# montaj_nrf24l01.net
KiCad netlist of a schematic drawn in EAGLE
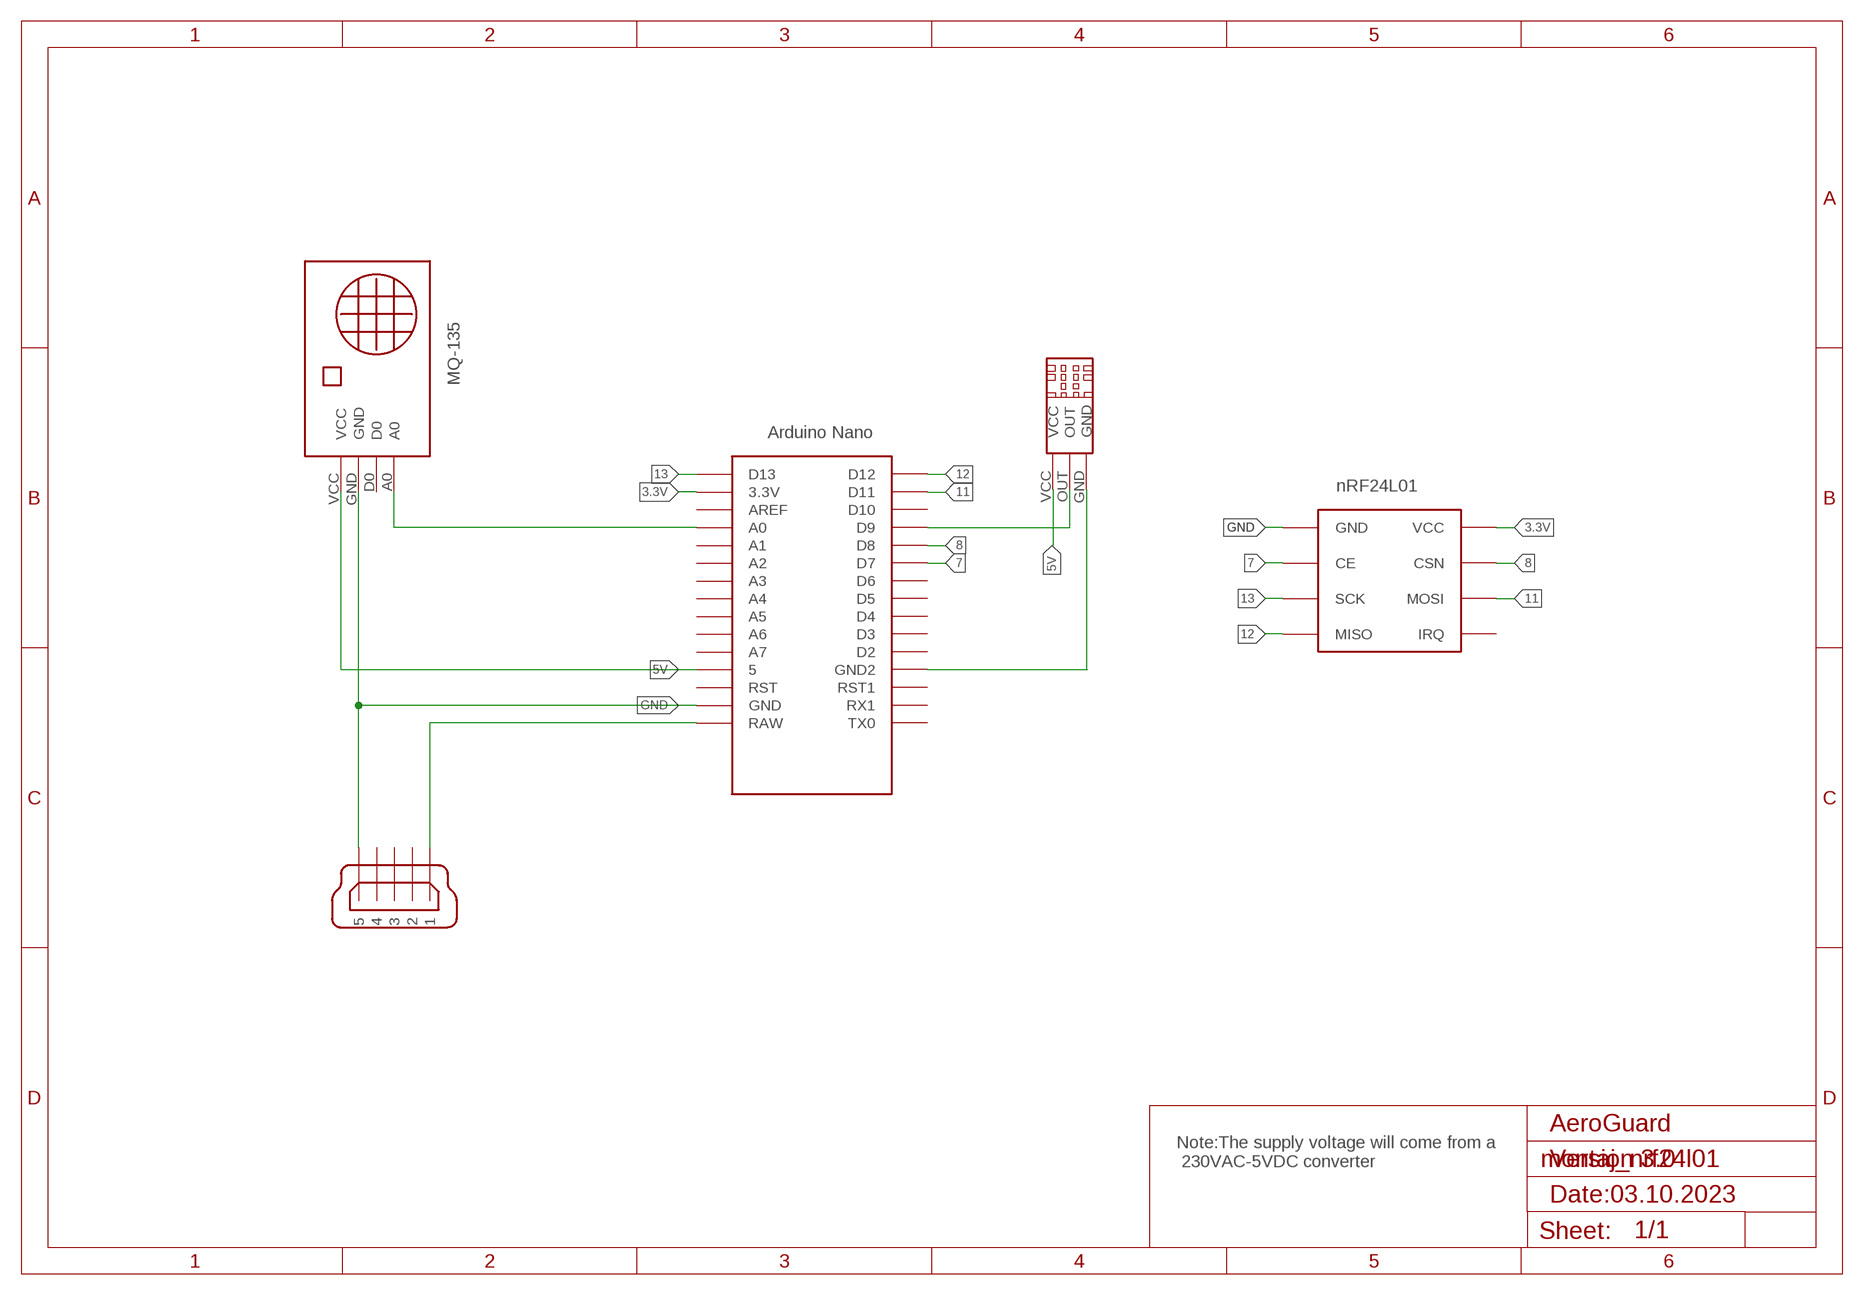
[diagram p0: schematic, sheet 1]

(export (version "E")
  (design (tool "Eeschema 10.0.6"))
  (components
    (comp (ref "GND")
      (value "NANO")
      (footprint "eagle-import:NANO")
      (libsource (lib "eagle-import") (part "NANO"))
    )
    (comp (ref "U$1")
      (value "DHT11")
      (footprint "eagle-import:DHT11")
      (libsource (lib "eagle-import") (part "DHT11"))
    )
    (comp (ref "U$2")
      (value "DEV")
      (footprint "eagle-import:FOOT")
      (libsource (lib "eagle-import") (part "DEV"))
    )
    (comp (ref "U$3")
      (value "NRF24L01")
      (footprint "eagle-import:NRF24L01")
      (libsource (lib "eagle-import") (part "NRF24L01"))
    )
    (comp (ref "X1")
      (value "MINI-USB-SHIELD-UX60-MB-5S8")
      (footprint "eagle-import:UX60-MB-5S8")
      (libsource (lib "eagle-import") (part "MINI-USB-SHIELD-UX60-MB-5S8"))
    )
  )
  (nets
    (net (code "1") (name "3.3V") (class "Default")
      (node (ref "U$3") (pin "VCC") (pinfunction "VCC_VCC") (pintype "bidirectional"))
    )
    (net (code "2") (name "5V") (class "Default")
      (node (ref "GND") (pin "5V") (pinfunction "5_5V") (pintype "bidirectional"))
      (node (ref "U$2") (pin "VCC") (pinfunction "VCC_VCC") (pintype "bidirectional"))
    )
    (net (code "3") (name "7") (class "Default")
      (node (ref "U$3") (pin "CE") (pinfunction "CE_CE") (pintype "bidirectional"))
    )
    (net (code "4") (name "8") (class "Default")
      (node (ref "U$3") (pin "CSN") (pinfunction "CSN_CSN") (pintype "bidirectional"))
    )
    (net (code "5") (name "11") (class "Default")
      (node (ref "U$3") (pin "MOSI") (pinfunction "MOSI_MOSI") (pintype "bidirectional"))
    )
    (net (code "6") (name "12") (class "Default")
      (node (ref "U$3") (pin "MISO") (pinfunction "MISO_MISO") (pintype "bidirectional"))
    )
    (net (code "7") (name "13") (class "Default")
      (node (ref "U$3") (pin "SCK") (pinfunction "SCK_SCK") (pintype "bidirectional"))
    )
    (net (code "8") (name "GND") (class "Default")
      (node (ref "U$3") (pin "GND") (pinfunction "GND_GND") (pintype "bidirectional"))
    )
    (net (code "9") (name "Net-(GND-GND2)") (class "Default")
      (node (ref "GND") (pin "GND1") (pinfunction "GND2_GND1") (pintype "bidirectional"))
      (node (ref "U$1") (pin "GND") (pinfunction "GND_GND") (pintype "bidirectional"))
    )
    (net (code "10") (name "Net-(GND-PadA0)") (class "Default")
      (node (ref "GND") (pin "A0") (pinfunction "A0_A0") (pintype "bidirectional"))
      (node (ref "U$2") (pin "A0") (pinfunction "A0_A0") (pintype "bidirectional"))
    )
    (net (code "11") (name "Net-(GND-PadD9)") (class "Default")
      (node (ref "GND") (pin "D9") (pinfunction "D9_D9") (pintype "bidirectional"))
      (node (ref "U$1") (pin "OUT") (pinfunction "OUT_OUT") (pintype "bidirectional"))
    )
    (net (code "12") (name "Net-(GND-PadGND)") (class "Default")
      (node (ref "GND") (pin "GND") (pinfunction "GND_GND") (pintype "bidirectional"))
      (node (ref "U$2") (pin "GND") (pinfunction "GND_GND") (pintype "bidirectional"))
      (node (ref "X1") (pin "5") (pinfunction "5_5") (pintype "input"))
    )
    (net (code "13") (name "Net-(GND-PadRAW)") (class "Default")
      (node (ref "GND") (pin "RAW") (pinfunction "RAW_RAW") (pintype "bidirectional"))
      (node (ref "X1") (pin "1") (pinfunction "1_1") (pintype "input"))
    )
    (net (code "14") (name "unconnected-(GND-Pad3.3V)") (class "Default")
      (node (ref "GND") (pin "3.3V") (pinfunction "3.3V_3.3V") (pintype "bidirectional"))
    )
    (net (code "15") (name "unconnected-(GND-PadA1)") (class "Default")
      (node (ref "GND") (pin "A1") (pinfunction "A1_A1") (pintype "bidirectional"))
    )
    (net (code "16") (name "unconnected-(GND-PadA2)") (class "Default")
      (node (ref "GND") (pin "A2") (pinfunction "A2_A2") (pintype "bidirectional"))
    )
    (net (code "17") (name "unconnected-(GND-PadA3)") (class "Default")
      (node (ref "GND") (pin "A3") (pinfunction "A3_A3") (pintype "bidirectional"))
    )
    (net (code "18") (name "unconnected-(GND-PadA4)") (class "Default")
      (node (ref "GND") (pin "A4") (pinfunction "A4_A4") (pintype "bidirectional"))
    )
    (net (code "19") (name "unconnected-(GND-PadA5)") (class "Default")
      (node (ref "GND") (pin "A5") (pinfunction "A5_A5") (pintype "bidirectional"))
    )
    (net (code "20") (name "unconnected-(GND-PadA6)") (class "Default")
      (node (ref "GND") (pin "A6") (pinfunction "A6_A6") (pintype "bidirectional"))
    )
    (net (code "21") (name "unconnected-(GND-PadA7)") (class "Default")
      (node (ref "GND") (pin "A7") (pinfunction "A7_A7") (pintype "bidirectional"))
    )
    (net (code "22") (name "unconnected-(GND-PadAREF)") (class "Default")
      (node (ref "GND") (pin "AREF") (pinfunction "AREF_AREF") (pintype "bidirectional"))
    )
    (net (code "23") (name "unconnected-(GND-PadD2)") (class "Default")
      (node (ref "GND") (pin "D2") (pinfunction "D2_D2") (pintype "bidirectional"))
    )
    (net (code "24") (name "unconnected-(GND-PadD3)") (class "Default")
      (node (ref "GND") (pin "D3") (pinfunction "D3_D3") (pintype "bidirectional"))
    )
    (net (code "25") (name "unconnected-(GND-PadD4)") (class "Default")
      (node (ref "GND") (pin "D4") (pinfunction "D4_D4") (pintype "bidirectional"))
    )
    (net (code "26") (name "unconnected-(GND-PadD5)") (class "Default")
      (node (ref "GND") (pin "D5") (pinfunction "D5_D5") (pintype "bidirectional"))
    )
    (net (code "27") (name "unconnected-(GND-PadD6)") (class "Default")
      (node (ref "GND") (pin "D6") (pinfunction "D6_D6") (pintype "bidirectional"))
    )
    (net (code "28") (name "unconnected-(GND-PadD7)") (class "Default")
      (node (ref "GND") (pin "D7") (pinfunction "D7_D7") (pintype "bidirectional"))
    )
    (net (code "29") (name "unconnected-(GND-PadD8)") (class "Default")
      (node (ref "GND") (pin "D8") (pinfunction "D8_D8") (pintype "bidirectional"))
    )
    (net (code "30") (name "unconnected-(GND-PadD10)") (class "Default")
      (node (ref "GND") (pin "D10") (pinfunction "D10_D10") (pintype "bidirectional"))
    )
    (net (code "31") (name "unconnected-(GND-PadD11)") (class "Default")
      (node (ref "GND") (pin "D11") (pinfunction "D11_D11") (pintype "bidirectional"))
    )
    (net (code "32") (name "unconnected-(GND-PadD12)") (class "Default")
      (node (ref "GND") (pin "D12") (pinfunction "D12_D12") (pintype "bidirectional"))
    )
    (net (code "33") (name "unconnected-(GND-PadD13)") (class "Default")
      (node (ref "GND") (pin "D13") (pinfunction "D13_D13") (pintype "bidirectional"))
    )
    (net (code "34") (name "unconnected-(GND-PadICSP1)") (class "Default")
      (node (ref "GND") (pin "ICSP1") (pinfunction "ICSP1_ICSP1") (pintype "bidirectional"))
    )
    (net (code "35") (name "unconnected-(GND-PadICSP2)") (class "Default")
      (node (ref "GND") (pin "ICSP2") (pinfunction "ICSP2_ICSP2") (pintype "bidirectional"))
    )
    (net (code "36") (name "unconnected-(GND-PadICSP3)") (class "Default")
      (node (ref "GND") (pin "ICSP3") (pinfunction "ICSP3_ICSP3") (pintype "bidirectional"))
    )
    (net (code "37") (name "unconnected-(GND-PadICSP4)") (class "Default")
      (node (ref "GND") (pin "ICSP4") (pinfunction "ICSP4_ICSP4") (pintype "bidirectional"))
    )
    (net (code "38") (name "unconnected-(GND-PadICSP5)") (class "Default")
      (node (ref "GND") (pin "ICSP5") (pinfunction "ICSP5_ICSP5") (pintype "bidirectional"))
    )
    (net (code "39") (name "unconnected-(GND-PadICSP6)") (class "Default")
      (node (ref "GND") (pin "ICSP6") (pinfunction "ICSP6_ICSP6") (pintype "bidirectional"))
    )
    (net (code "40") (name "unconnected-(GND-PadRST)") (class "Default")
      (node (ref "GND") (pin "RST") (pinfunction "RST_RST") (pintype "bidirectional"))
    )
    (net (code "41") (name "unconnected-(GND-PadRST1)") (class "Default")
      (node (ref "GND") (pin "RST1") (pinfunction "RST1_RST1") (pintype "bidirectional"))
    )
    (net (code "42") (name "unconnected-(GND-PadRX1)") (class "Default")
      (node (ref "GND") (pin "RX1") (pinfunction "RX1_RX1") (pintype "bidirectional"))
    )
    (net (code "43") (name "unconnected-(GND-PadTX0)") (class "Default")
      (node (ref "GND") (pin "TX0") (pinfunction "TX0_TX0") (pintype "bidirectional"))
    )
    (net (code "44") (name "unconnected-(U$1-PadVCC)") (class "Default")
      (node (ref "U$1") (pin "VCC") (pinfunction "VCC_VCC") (pintype "bidirectional"))
    )
    (net (code "45") (name "unconnected-(U$2-PadD0)") (class "Default")
      (node (ref "U$2") (pin "D0") (pinfunction "D0_D0") (pintype "bidirectional"))
    )
    (net (code "46") (name "unconnected-(U$3-PadIRQ)") (class "Default")
      (node (ref "U$3") (pin "IRQ") (pinfunction "IRQ_IRQ") (pintype "bidirectional"))
    )
    (net (code "47") (name "unconnected-(X1-Pad2)") (class "Default")
      (node (ref "X1") (pin "2") (pinfunction "2_2") (pintype "input"))
    )
    (net (code "48") (name "unconnected-(X1-Pad3)") (class "Default")
      (node (ref "X1") (pin "3") (pinfunction "3_3") (pintype "input"))
    )
    (net (code "49") (name "unconnected-(X1-Pad4)") (class "Default")
      (node (ref "X1") (pin "4") (pinfunction "4_4") (pintype "input"))
    )
  )
)
